# 18650_Battery_Tray.net
KiCad netlist of a schematic drawn in EAGLE
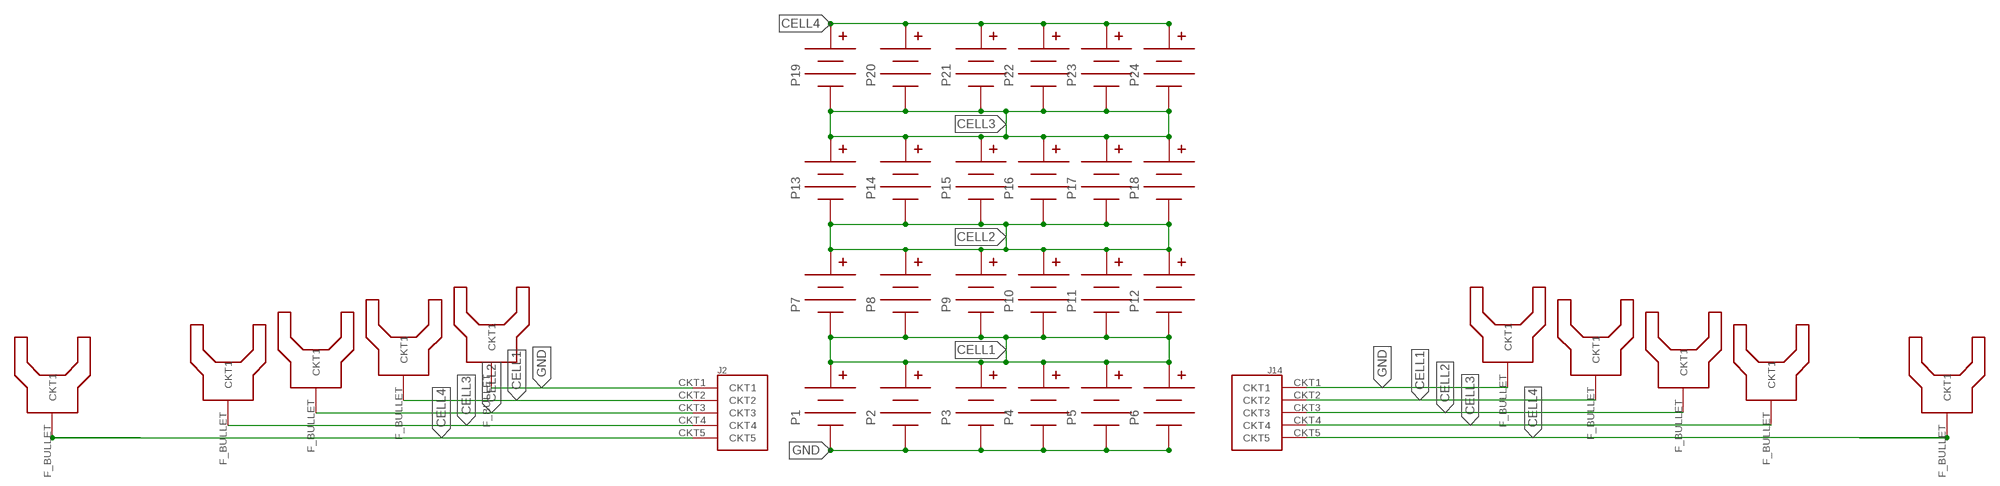
[diagram p0: schematic, sheet 1]

(export (version "E")
  (design (tool "Eeschema 10.0.6"))
  (components
    (comp (ref "J1")
      (value "FEMALE_BULLET")
      (footprint "eagle-import:FEMALE_BULLET_CONNECTOR_6MM")
      (libsource (lib "eagle-import") (part "FEMALE_BULLET"))
    )
    (comp (ref "J2")
      (value "MOLEX_NANO_FIT_5CT_VERTICAL_HEADER")
      (footprint "eagle-import:MOLEX_NANO_FIT_5_VERTICAL_HEADER")
      (libsource (lib "eagle-import") (part "MOLEX_NANO_FIT_5CT_VERTICAL_HEADER"))
    )
    (comp (ref "J3")
      (value "FEMALE_BULLET")
      (footprint "eagle-import:FEMALE_BULLET_CONNECTOR_6MM")
      (libsource (lib "eagle-import") (part "FEMALE_BULLET"))
    )
    (comp (ref "J4")
      (value "FEMALE_BULLET")
      (footprint "eagle-import:FEMALE_BULLET_CONNECTOR_6MM")
      (libsource (lib "eagle-import") (part "FEMALE_BULLET"))
    )
    (comp (ref "J5")
      (value "FEMALE_BULLET")
      (footprint "eagle-import:FEMALE_BULLET_CONNECTOR_6MM")
      (libsource (lib "eagle-import") (part "FEMALE_BULLET"))
    )
    (comp (ref "J7")
      (value "FEMALE_BULLET")
      (footprint "eagle-import:FEMALE_BULLET_CONNECTOR_6MM")
      (libsource (lib "eagle-import") (part "FEMALE_BULLET"))
    )
    (comp (ref "J9")
      (value "FEMALE_BULLET")
      (footprint "eagle-import:FEMALE_BULLET_CONNECTOR_6MM")
      (libsource (lib "eagle-import") (part "FEMALE_BULLET"))
    )
    (comp (ref "J10")
      (value "FEMALE_BULLET")
      (footprint "eagle-import:FEMALE_BULLET_CONNECTOR_6MM")
      (libsource (lib "eagle-import") (part "FEMALE_BULLET"))
    )
    (comp (ref "J11")
      (value "FEMALE_BULLET")
      (footprint "eagle-import:FEMALE_BULLET_CONNECTOR_6MM")
      (libsource (lib "eagle-import") (part "FEMALE_BULLET"))
    )
    (comp (ref "J12")
      (value "FEMALE_BULLET")
      (footprint "eagle-import:FEMALE_BULLET_CONNECTOR_6MM")
      (libsource (lib "eagle-import") (part "FEMALE_BULLET"))
    )
    (comp (ref "J14")
      (value "MOLEX_NANO_FIT_5CT_VERTICAL_HEADER")
      (footprint "eagle-import:MOLEX_NANO_FIT_5_VERTICAL_HEADER")
      (libsource (lib "eagle-import") (part "MOLEX_NANO_FIT_5CT_VERTICAL_HEADER"))
    )
    (comp (ref "J15")
      (value "FEMALE_BULLET")
      (footprint "eagle-import:FEMALE_BULLET_CONNECTOR_6MM")
      (libsource (lib "eagle-import") (part "FEMALE_BULLET"))
    )
    (comp (ref "P1")
      (value "18650_BAT_TRAY_SMD_NON_POLAR")
      (footprint "eagle-import:18650_BAT_TRAY_SMD_NON_POLAR")
      (libsource (lib "eagle-import") (part "18650_BAT_TRAY_SMD_NON_POLAR"))
    )
    (comp (ref "P2")
      (value "18650_BAT_TRAY_SMD_NON_POLAR")
      (footprint "eagle-import:18650_BAT_TRAY_SMD_NON_POLAR")
      (libsource (lib "eagle-import") (part "18650_BAT_TRAY_SMD_NON_POLAR"))
    )
    (comp (ref "P3")
      (value "18650_BAT_TRAY_SMD_NON_POLAR")
      (footprint "eagle-import:18650_BAT_TRAY_SMD_NON_POLAR")
      (libsource (lib "eagle-import") (part "18650_BAT_TRAY_SMD_NON_POLAR"))
    )
    (comp (ref "P4")
      (value "18650_BAT_TRAY_SMD_NON_POLAR")
      (footprint "eagle-import:18650_BAT_TRAY_SMD_NON_POLAR")
      (libsource (lib "eagle-import") (part "18650_BAT_TRAY_SMD_NON_POLAR"))
    )
    (comp (ref "P5")
      (value "18650_BAT_TRAY_SMD_NON_POLAR")
      (footprint "eagle-import:18650_BAT_TRAY_SMD_NON_POLAR")
      (libsource (lib "eagle-import") (part "18650_BAT_TRAY_SMD_NON_POLAR"))
    )
    (comp (ref "P6")
      (value "18650_BAT_TRAY_SMD_NON_POLAR")
      (footprint "eagle-import:18650_BAT_TRAY_SMD_NON_POLAR")
      (libsource (lib "eagle-import") (part "18650_BAT_TRAY_SMD_NON_POLAR"))
    )
    (comp (ref "P7")
      (value "18650_BAT_TRAY_SMD_NON_POLAR")
      (footprint "eagle-import:18650_BAT_TRAY_SMD_NON_POLAR")
      (libsource (lib "eagle-import") (part "18650_BAT_TRAY_SMD_NON_POLAR"))
    )
    (comp (ref "P8")
      (value "18650_BAT_TRAY_SMD_NON_POLAR")
      (footprint "eagle-import:18650_BAT_TRAY_SMD_NON_POLAR")
      (libsource (lib "eagle-import") (part "18650_BAT_TRAY_SMD_NON_POLAR"))
    )
    (comp (ref "P9")
      (value "18650_BAT_TRAY_SMD_NON_POLAR")
      (footprint "eagle-import:18650_BAT_TRAY_SMD_NON_POLAR")
      (libsource (lib "eagle-import") (part "18650_BAT_TRAY_SMD_NON_POLAR"))
    )
    (comp (ref "P10")
      (value "18650_BAT_TRAY_SMD_NON_POLAR")
      (footprint "eagle-import:18650_BAT_TRAY_SMD_NON_POLAR")
      (libsource (lib "eagle-import") (part "18650_BAT_TRAY_SMD_NON_POLAR"))
    )
    (comp (ref "P11")
      (value "18650_BAT_TRAY_SMD_NON_POLAR")
      (footprint "eagle-import:18650_BAT_TRAY_SMD_NON_POLAR")
      (libsource (lib "eagle-import") (part "18650_BAT_TRAY_SMD_NON_POLAR"))
    )
    (comp (ref "P12")
      (value "18650_BAT_TRAY_SMD_NON_POLAR")
      (footprint "eagle-import:18650_BAT_TRAY_SMD_NON_POLAR")
      (libsource (lib "eagle-import") (part "18650_BAT_TRAY_SMD_NON_POLAR"))
    )
    (comp (ref "P13")
      (value "18650_BAT_TRAY_SMD_NON_POLAR")
      (footprint "eagle-import:18650_BAT_TRAY_SMD_NON_POLAR")
      (libsource (lib "eagle-import") (part "18650_BAT_TRAY_SMD_NON_POLAR"))
    )
    (comp (ref "P14")
      (value "18650_BAT_TRAY_SMD_NON_POLAR")
      (footprint "eagle-import:18650_BAT_TRAY_SMD_NON_POLAR")
      (libsource (lib "eagle-import") (part "18650_BAT_TRAY_SMD_NON_POLAR"))
    )
    (comp (ref "P15")
      (value "18650_BAT_TRAY_SMD_NON_POLAR")
      (footprint "eagle-import:18650_BAT_TRAY_SMD_NON_POLAR")
      (libsource (lib "eagle-import") (part "18650_BAT_TRAY_SMD_NON_POLAR"))
    )
    (comp (ref "P16")
      (value "18650_BAT_TRAY_SMD_NON_POLAR")
      (footprint "eagle-import:18650_BAT_TRAY_SMD_NON_POLAR")
      (libsource (lib "eagle-import") (part "18650_BAT_TRAY_SMD_NON_POLAR"))
    )
    (comp (ref "P17")
      (value "18650_BAT_TRAY_SMD_NON_POLAR")
      (footprint "eagle-import:18650_BAT_TRAY_SMD_NON_POLAR")
      (libsource (lib "eagle-import") (part "18650_BAT_TRAY_SMD_NON_POLAR"))
    )
    (comp (ref "P18")
      (value "18650_BAT_TRAY_SMD_NON_POLAR")
      (footprint "eagle-import:18650_BAT_TRAY_SMD_NON_POLAR")
      (libsource (lib "eagle-import") (part "18650_BAT_TRAY_SMD_NON_POLAR"))
    )
    (comp (ref "P19")
      (value "18650_BAT_TRAY_SMD_NON_POLAR")
      (footprint "eagle-import:18650_BAT_TRAY_SMD_NON_POLAR")
      (libsource (lib "eagle-import") (part "18650_BAT_TRAY_SMD_NON_POLAR"))
    )
    (comp (ref "P20")
      (value "18650_BAT_TRAY_SMD_NON_POLAR")
      (footprint "eagle-import:18650_BAT_TRAY_SMD_NON_POLAR")
      (libsource (lib "eagle-import") (part "18650_BAT_TRAY_SMD_NON_POLAR"))
    )
    (comp (ref "P21")
      (value "18650_BAT_TRAY_SMD_NON_POLAR")
      (footprint "eagle-import:18650_BAT_TRAY_SMD_NON_POLAR")
      (libsource (lib "eagle-import") (part "18650_BAT_TRAY_SMD_NON_POLAR"))
    )
    (comp (ref "P22")
      (value "18650_BAT_TRAY_SMD_NON_POLAR")
      (footprint "eagle-import:18650_BAT_TRAY_SMD_NON_POLAR")
      (libsource (lib "eagle-import") (part "18650_BAT_TRAY_SMD_NON_POLAR"))
    )
    (comp (ref "P23")
      (value "18650_BAT_TRAY_SMD_NON_POLAR")
      (footprint "eagle-import:18650_BAT_TRAY_SMD_NON_POLAR")
      (libsource (lib "eagle-import") (part "18650_BAT_TRAY_SMD_NON_POLAR"))
    )
    (comp (ref "P24")
      (value "18650_BAT_TRAY_SMD_NON_POLAR")
      (footprint "eagle-import:18650_BAT_TRAY_SMD_NON_POLAR")
      (libsource (lib "eagle-import") (part "18650_BAT_TRAY_SMD_NON_POLAR"))
    )
  )
  (nets
    (net (code "1") (name "CELL1") (class "Default")
      (node (ref "J10") (pin "F_BULLET") (pinfunction "CKT1_F_BULLET") (pintype "bidirectional"))
      (node (ref "J14") (pin "CKT2") (pinfunction "CKT2_CKT2") (pintype "bidirectional"))
      (node (ref "J2") (pin "CKT2") (pinfunction "CKT2_CKT2") (pintype "bidirectional"))
      (node (ref "J3") (pin "F_BULLET") (pinfunction "CKT1_F_BULLET") (pintype "bidirectional"))
      (node (ref "P1") (pin "P$2") (pinfunction "V+_P$2") (pintype "bidirectional"))
      (node (ref "P10") (pin "P$1") (pinfunction "V-_P$1") (pintype "bidirectional"))
      (node (ref "P11") (pin "P$1") (pinfunction "V-_P$1") (pintype "bidirectional"))
      (node (ref "P12") (pin "P$1") (pinfunction "V-_P$1") (pintype "bidirectional"))
      (node (ref "P2") (pin "P$2") (pinfunction "V+_P$2") (pintype "bidirectional"))
      (node (ref "P3") (pin "P$2") (pinfunction "V+_P$2") (pintype "bidirectional"))
      (node (ref "P4") (pin "P$2") (pinfunction "V+_P$2") (pintype "bidirectional"))
      (node (ref "P5") (pin "P$2") (pinfunction "V+_P$2") (pintype "bidirectional"))
      (node (ref "P6") (pin "P$2") (pinfunction "V+_P$2") (pintype "bidirectional"))
      (node (ref "P7") (pin "P$1") (pinfunction "V-_P$1") (pintype "bidirectional"))
      (node (ref "P8") (pin "P$1") (pinfunction "V-_P$1") (pintype "bidirectional"))
      (node (ref "P9") (pin "P$1") (pinfunction "V-_P$1") (pintype "bidirectional"))
    )
    (net (code "2") (name "CELL2") (class "Default")
      (node (ref "J11") (pin "F_BULLET") (pinfunction "CKT1_F_BULLET") (pintype "bidirectional"))
      (node (ref "J14") (pin "CKT3") (pinfunction "CKT3_CKT3") (pintype "bidirectional"))
      (node (ref "J2") (pin "CKT3") (pinfunction "CKT3_CKT3") (pintype "bidirectional"))
      (node (ref "J4") (pin "F_BULLET") (pinfunction "CKT1_F_BULLET") (pintype "bidirectional"))
      (node (ref "P10") (pin "P$2") (pinfunction "V+_P$2") (pintype "bidirectional"))
      (node (ref "P11") (pin "P$2") (pinfunction "V+_P$2") (pintype "bidirectional"))
      (node (ref "P12") (pin "P$2") (pinfunction "V+_P$2") (pintype "bidirectional"))
      (node (ref "P13") (pin "P$1") (pinfunction "V-_P$1") (pintype "bidirectional"))
      (node (ref "P14") (pin "P$1") (pinfunction "V-_P$1") (pintype "bidirectional"))
      (node (ref "P15") (pin "P$1") (pinfunction "V-_P$1") (pintype "bidirectional"))
      (node (ref "P16") (pin "P$1") (pinfunction "V-_P$1") (pintype "bidirectional"))
      (node (ref "P17") (pin "P$1") (pinfunction "V-_P$1") (pintype "bidirectional"))
      (node (ref "P18") (pin "P$1") (pinfunction "V-_P$1") (pintype "bidirectional"))
      (node (ref "P7") (pin "P$2") (pinfunction "V+_P$2") (pintype "bidirectional"))
      (node (ref "P8") (pin "P$2") (pinfunction "V+_P$2") (pintype "bidirectional"))
      (node (ref "P9") (pin "P$2") (pinfunction "V+_P$2") (pintype "bidirectional"))
    )
    (net (code "3") (name "CELL3") (class "Default")
      (node (ref "J12") (pin "F_BULLET") (pinfunction "CKT1_F_BULLET") (pintype "bidirectional"))
      (node (ref "J14") (pin "CKT4") (pinfunction "CKT4_CKT4") (pintype "bidirectional"))
      (node (ref "J2") (pin "CKT4") (pinfunction "CKT4_CKT4") (pintype "bidirectional"))
      (node (ref "J5") (pin "F_BULLET") (pinfunction "CKT1_F_BULLET") (pintype "bidirectional"))
      (node (ref "P13") (pin "P$2") (pinfunction "V+_P$2") (pintype "bidirectional"))
      (node (ref "P14") (pin "P$2") (pinfunction "V+_P$2") (pintype "bidirectional"))
      (node (ref "P15") (pin "P$2") (pinfunction "V+_P$2") (pintype "bidirectional"))
      (node (ref "P16") (pin "P$2") (pinfunction "V+_P$2") (pintype "bidirectional"))
      (node (ref "P17") (pin "P$2") (pinfunction "V+_P$2") (pintype "bidirectional"))
      (node (ref "P18") (pin "P$2") (pinfunction "V+_P$2") (pintype "bidirectional"))
      (node (ref "P19") (pin "P$1") (pinfunction "V-_P$1") (pintype "bidirectional"))
      (node (ref "P20") (pin "P$1") (pinfunction "V-_P$1") (pintype "bidirectional"))
      (node (ref "P21") (pin "P$1") (pinfunction "V-_P$1") (pintype "bidirectional"))
      (node (ref "P22") (pin "P$1") (pinfunction "V-_P$1") (pintype "bidirectional"))
      (node (ref "P23") (pin "P$1") (pinfunction "V-_P$1") (pintype "bidirectional"))
      (node (ref "P24") (pin "P$1") (pinfunction "V-_P$1") (pintype "bidirectional"))
    )
    (net (code "4") (name "CELL4") (class "Default")
      (node (ref "J14") (pin "CKT5") (pinfunction "CKT5_CKT5") (pintype "bidirectional"))
      (node (ref "J15") (pin "F_BULLET") (pinfunction "CKT1_F_BULLET") (pintype "bidirectional"))
      (node (ref "J2") (pin "CKT5") (pinfunction "CKT5_CKT5") (pintype "bidirectional"))
      (node (ref "J7") (pin "F_BULLET") (pinfunction "CKT1_F_BULLET") (pintype "bidirectional"))
      (node (ref "P19") (pin "P$2") (pinfunction "V+_P$2") (pintype "bidirectional"))
      (node (ref "P20") (pin "P$2") (pinfunction "V+_P$2") (pintype "bidirectional"))
      (node (ref "P21") (pin "P$2") (pinfunction "V+_P$2") (pintype "bidirectional"))
      (node (ref "P22") (pin "P$2") (pinfunction "V+_P$2") (pintype "bidirectional"))
      (node (ref "P23") (pin "P$2") (pinfunction "V+_P$2") (pintype "bidirectional"))
      (node (ref "P24") (pin "P$2") (pinfunction "V+_P$2") (pintype "bidirectional"))
    )
    (net (code "5") (name "GND") (class "Default")
      (node (ref "J1") (pin "F_BULLET") (pinfunction "CKT1_F_BULLET") (pintype "bidirectional"))
      (node (ref "J14") (pin "CKT1") (pinfunction "CKT1_CKT1") (pintype "bidirectional"))
      (node (ref "J2") (pin "CKT1") (pinfunction "CKT1_CKT1") (pintype "bidirectional"))
      (node (ref "J9") (pin "F_BULLET") (pinfunction "CKT1_F_BULLET") (pintype "bidirectional"))
      (node (ref "P1") (pin "P$1") (pinfunction "V-_P$1") (pintype "bidirectional"))
      (node (ref "P2") (pin "P$1") (pinfunction "V-_P$1") (pintype "bidirectional"))
      (node (ref "P3") (pin "P$1") (pinfunction "V-_P$1") (pintype "bidirectional"))
      (node (ref "P4") (pin "P$1") (pinfunction "V-_P$1") (pintype "bidirectional"))
      (node (ref "P5") (pin "P$1") (pinfunction "V-_P$1") (pintype "bidirectional"))
      (node (ref "P6") (pin "P$1") (pinfunction "V-_P$1") (pintype "bidirectional"))
    )
  )
)
